# Power.net
KiCad netlist of a schematic drawn in Altium Designer
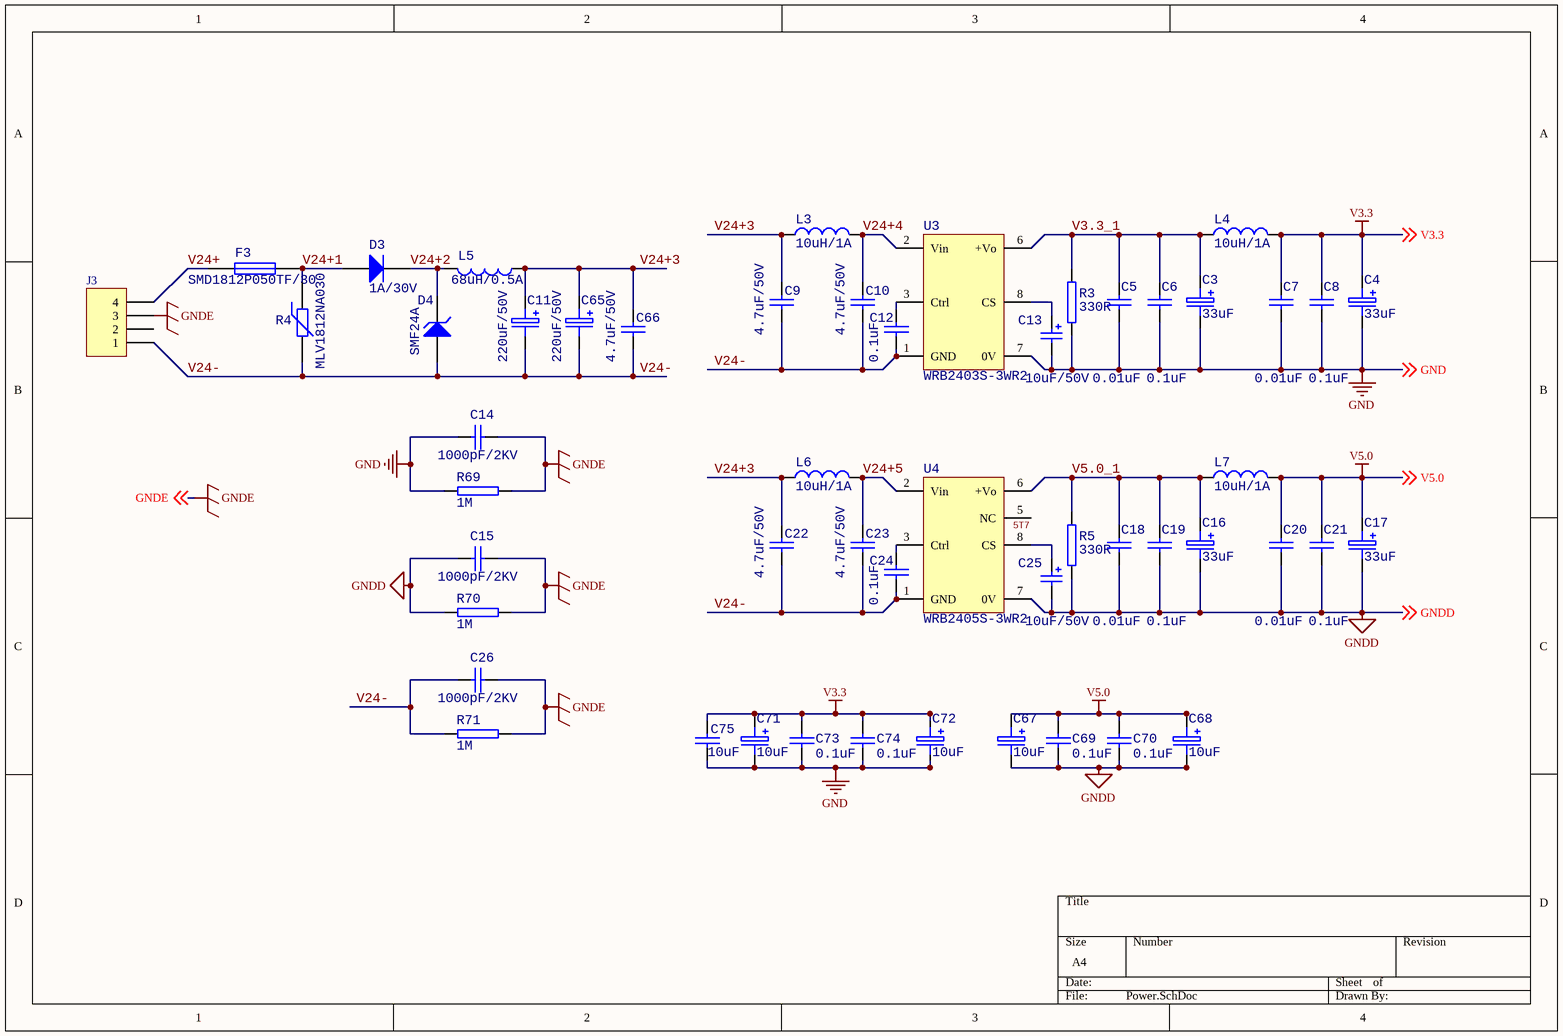
[diagram p0: Power.SchDoc]

(export (version "E")
  (design (tool "Eeschema 10.0.6"))
  (components
    (comp (ref "C3")
      (value "33uF")
      (footprint "C3528(B)")
      (description "CA45-?V?uF ABCD 16V10UF[A型3210]16V22UF(B型1210) 16V47UF(C型1812)")
      (libsource (lib "input") (part "CAPACITOR POL"))
    )
    (comp (ref "C4")
      (value "33uF")
      (footprint "C3528(B)")
      (description "CA45-?V?uF ABCD 16V10UF[A型3210]16V22UF(B型1210) 16V47UF(C型1812)")
      (libsource (lib "input") (part "CAPACITOR POL"))
    )
    (comp (ref "C5")
      (value "0.01uF")
      (footprint "C1608(0603)")
      (description "Capacitor")
      (libsource (lib "input") (part "CAP"))
    )
    (comp (ref "C6")
      (value "0.1uF")
      (footprint "C1608(0603)")
      (description "Capacitor")
      (libsource (lib "input") (part "CAP"))
    )
    (comp (ref "C7")
      (value "0.01uF")
      (footprint "C1608(0603)")
      (description "Capacitor")
      (libsource (lib "input") (part "CAP"))
    )
    (comp (ref "C8")
      (value "0.1uF")
      (footprint "C1608(0603)")
      (description "Capacitor")
      (libsource (lib "input") (part "CAP"))
    )
    (comp (ref "C9")
      (value "4.7uF/50V")
      (footprint "C2012(0805)")
      (description "Capacitor")
      (libsource (lib "input") (part "CAP"))
    )
    (comp (ref "C10")
      (value "4.7uF/50V")
      (footprint "C2012(0805)")
      (description "Capacitor")
      (libsource (lib "input") (part "CAP"))
    )
    (comp (ref "C11")
      (value "220uF/50V")
      (footprint "CAPMP10X120")
      (description "CA45-?V?uF ABCD 16V10UF[A型3210]16V22UF(B型1210) 16V47UF(C型1812)")
      (libsource (lib "input") (part "CAPACITOR POL"))
    )
    (comp (ref "C12")
      (value "0.1uF")
      (footprint "C1608(0603)")
      (description "Capacitor")
      (libsource (lib "input") (part "CAP"))
    )
    (comp (ref "C13")
      (value "10uF/50V")
      (footprint "C3216(1206)")
      (description "Polarized Capacitor (Axial)")
      (fields (field (name "PUBLISHER") "Altium Limited"))
      (libsource (lib "Miscellaneous Devices") (part "Cap Pol2"))
    )
    (comp (ref "C14")
      (value "1000pF/2KV")
      (footprint "C3216(1206)")
      (description "Capacitor")
      (libsource (lib "input") (part "CAP"))
    )
    (comp (ref "C15")
      (value "1000pF/2KV")
      (footprint "C3216(1206)")
      (description "Capacitor")
      (libsource (lib "input") (part "CAP"))
    )
    (comp (ref "C16")
      (value "33uF")
      (footprint "C3528(B)")
      (description "CA45-?V?uF ABCD 16V10UF[A型3210]16V22UF(B型1210) 16V47UF(C型1812)")
      (libsource (lib "input") (part "CAPACITOR POL"))
    )
    (comp (ref "C17")
      (value "33uF")
      (footprint "C3528(B)")
      (description "CA45-?V?uF ABCD 16V10UF[A型3210]16V22UF(B型1210) 16V47UF(C型1812)")
      (libsource (lib "input") (part "CAPACITOR POL"))
    )
    (comp (ref "C18")
      (value "0.01uF")
      (footprint "C1608(0603)")
      (description "Capacitor")
      (libsource (lib "input") (part "CAP"))
    )
    (comp (ref "C19")
      (value "0.1uF")
      (footprint "C1608(0603)")
      (description "Capacitor")
      (libsource (lib "input") (part "CAP"))
    )
    (comp (ref "C20")
      (value "0.01uF")
      (footprint "C1608(0603)")
      (description "Capacitor")
      (libsource (lib "input") (part "CAP"))
    )
    (comp (ref "C21")
      (value "0.1uF")
      (footprint "C1608(0603)")
      (description "Capacitor")
      (libsource (lib "input") (part "CAP"))
    )
    (comp (ref "C22")
      (value "4.7uF/50V")
      (footprint "C2012(0805)")
      (description "Capacitor")
      (libsource (lib "input") (part "CAP"))
    )
    (comp (ref "C23")
      (value "4.7uF/50V")
      (footprint "C2012(0805)")
      (description "Capacitor")
      (libsource (lib "input") (part "CAP"))
    )
    (comp (ref "C24")
      (value "0.1uF")
      (footprint "C1608(0603)")
      (description "Capacitor")
      (libsource (lib "input") (part "CAP"))
    )
    (comp (ref "C25")
      (value "10uF/50V")
      (footprint "C3216(1206)")
      (description "Polarized Capacitor (Axial)")
      (fields (field (name "PUBLISHER") "Altium Limited"))
      (libsource (lib "Miscellaneous Devices") (part "Cap Pol2"))
    )
    (comp (ref "C26")
      (value "1000pF/2KV")
      (footprint "C3216(1206)")
      (description "Capacitor")
      (libsource (lib "input") (part "CAP"))
    )
    (comp (ref "C65")
      (value "220uF/50V")
      (footprint "CAPMP10X120")
      (description "CA45-?V?uF ABCD 16V10UF[A型3210]16V22UF(B型1210) 16V47UF(C型1812)")
      (libsource (lib "input") (part "CAPACITOR POL"))
    )
    (comp (ref "C66")
      (value "4.7uF/50V")
      (footprint "C2012(0805)")
      (description "Capacitor")
      (libsource (lib "input") (part "CAP"))
    )
    (comp (ref "C67")
      (value "10uF")
      (footprint "C3216(A)")
      (description "CA45-?V?uF ABCD 16V10UF[A型3210]16V22UF(B型1210) 16V47UF(C型1812)")
      (libsource (lib "input") (part "CAPACITOR POL"))
    )
    (comp (ref "C68")
      (value "10uF")
      (footprint "C3216(A)")
      (description "CA45-?V?uF ABCD 16V10UF[A型3210]16V22UF(B型1210) 16V47UF(C型1812)")
      (libsource (lib "input") (part "CAPACITOR POL"))
    )
    (comp (ref "C69")
      (value "0.1uF")
      (footprint "C1608(0603)")
      (description "Capacitor")
      (libsource (lib "input") (part "CAP"))
    )
    (comp (ref "C70")
      (value "0.1uF")
      (footprint "C1608(0603)")
      (description "Capacitor")
      (libsource (lib "input") (part "CAP"))
    )
    (comp (ref "C71")
      (value "10uF")
      (footprint "C3216(A)")
      (description "CA45-?V?uF ABCD 16V10UF[A型3210]16V22UF(B型1210) 16V47UF(C型1812)")
      (libsource (lib "input") (part "CAPACITOR POL"))
    )
    (comp (ref "C72")
      (value "10uF")
      (footprint "C3216(A)")
      (description "CA45-?V?uF ABCD 16V10UF[A型3210]16V22UF(B型1210) 16V47UF(C型1812)")
      (libsource (lib "input") (part "CAPACITOR POL"))
    )
    (comp (ref "C73")
      (value "0.1uF")
      (footprint "C1608(0603)")
      (description "Capacitor")
      (libsource (lib "input") (part "CAP"))
    )
    (comp (ref "C74")
      (value "0.1uF")
      (footprint "C1608(0603)")
      (description "Capacitor")
      (libsource (lib "input") (part "CAP"))
    )
    (comp (ref "C75")
      (value "10uF")
      (footprint "C2012(0805)")
      (description "Capacitor")
      (libsource (lib "input") (part "CAP"))
    )
    (comp (ref "D3")
      (value "1A/30V")
      (footprint "SOD323")
      (description "Default Diode")
      (fields (field (name "PUBLISHER") "Altium Limited"))
      (libsource (lib "Miscellaneous Devices") (part "Diode"))
    )
    (comp (ref "D4")
      (value "SMF24A")
      (footprint "SOD123")
      (description "Zener Diode")
      (fields (field (name "PUBLISHER") "Altium Limited"))
      (libsource (lib "Miscellaneous Devices") (part "D Zener"))
    )
    (comp (ref "F3")
      (value "SMD1812P050TF/30")
      (footprint "R4532(1812)")
      (description "Fuse")
      (libsource (lib "*") (part "FUSE1"))
    )
    (comp (ref "J3")
      (value "Header 4")
      (footprint "MSTBO2.5/4-G1R")
      (description "Header, 4-Pin")
      (fields (field (name "PUBLISHER") "Altium Limited"))
      (libsource (lib "Miscellaneous Connectors") (part "Header 4"))
    )
    (comp (ref "L3")
      (value "10uH/1A")
      (footprint "L4040")
      (description "Inductor")
      (fields (field (name "PUBLISHER") "Altium Limited"))
      (libsource (lib "Miscellaneous Devices") (part "Inductor"))
    )
    (comp (ref "L4")
      (value "10uH/1A")
      (footprint "L4040")
      (description "Inductor")
      (fields (field (name "PUBLISHER") "Altium Limited"))
      (libsource (lib "Miscellaneous Devices") (part "Inductor"))
    )
    (comp (ref "L5")
      (value "68uH/0.5A")
      (footprint "L4040")
      (description "Inductor")
      (fields (field (name "PUBLISHER") "Altium Limited"))
      (libsource (lib "Miscellaneous Devices") (part "Inductor"))
    )
    (comp (ref "L6")
      (value "10uH/1A")
      (footprint "L4040")
      (description "Inductor")
      (fields (field (name "PUBLISHER") "Altium Limited"))
      (libsource (lib "Miscellaneous Devices") (part "Inductor"))
    )
    (comp (ref "L7")
      (value "10uH/1A")
      (footprint "L4040")
      (description "Inductor")
      (fields (field (name "PUBLISHER") "Altium Limited"))
      (libsource (lib "Miscellaneous Devices") (part "Inductor"))
    )
    (comp (ref "R3") (value "330R") (footprint "R3216(1206)") (libsource (lib "motor") (part "R")))
    (comp (ref "R4")
      (value "MLV1812NA030")
      (footprint "R4532(1812)")
      (description "Varistor (Voltage-Sensitive Resistor)")
      (fields (field (name "PUBLISHER") "Altium Limited"))
      (libsource (lib "Miscellaneous Devices") (part "Res Varistor"))
    )
    (comp (ref "R5") (value "330R") (footprint "R3216(1206)") (libsource (lib "motor") (part "R")))
    (comp (ref "R69") (value "1M") (footprint "R3216(1206)") (libsource (lib "motor") (part "R")))
    (comp (ref "R70") (value "1M") (footprint "R3216(1206)") (libsource (lib "motor") (part "R")))
    (comp (ref "R71") (value "1M") (footprint "R3216(1206)") (libsource (lib "motor") (part "R")))
    (comp (ref "U3")
      (value "WRB2403S-3WR2")
      (footprint "SIP8")
      (libsource (lib "SL-DPT100") (part "WRA_S-1WR2"))
    )
    (comp (ref "U4")
      (value "WRB2405S-3WR2")
      (footprint "SIP8")
      (libsource (lib "SL-DPT100") (part "WRA_S-1WR2"))
    )
  )
  (nets
    (net (code "1") (name "/5T7") (class "Default")
      (node (ref "U4") (pin "5") (pinfunction "NC_5") (pintype "passive"))
    )
    (net (code "2") (name "/V3.3_1") (class "Default")
      (node (ref "C3") (pin "1") (pinfunction "1_1") (pintype "passive"))
      (node (ref "C5") (pin "2") (pinfunction "2_2") (pintype "passive"))
      (node (ref "C6") (pin "2") (pinfunction "2_2") (pintype "passive"))
      (node (ref "L4") (pin "1") (pinfunction "1_1") (pintype "passive"))
      (node (ref "R3") (pin "1") (pinfunction "1_1") (pintype "passive"))
      (node (ref "U3") (pin "6") (pinfunction "+Vo_6") (pintype "passive"))
    )
    (net (code "3") (name "/V5.0_1") (class "Default")
      (node (ref "C16") (pin "1") (pinfunction "1_1") (pintype "passive"))
      (node (ref "C18") (pin "2") (pinfunction "2_2") (pintype "passive"))
      (node (ref "C19") (pin "2") (pinfunction "2_2") (pintype "passive"))
      (node (ref "L7") (pin "1") (pinfunction "1_1") (pintype "passive"))
      (node (ref "R5") (pin "1") (pinfunction "1_1") (pintype "passive"))
      (node (ref "U4") (pin "6") (pinfunction "+Vo_6") (pintype "passive"))
    )
    (net (code "4") (name "/V24+") (class "Default")
      (node (ref "F3") (pin "1") (pinfunction "1_1") (pintype "passive"))
      (node (ref "J3") (pin "4") (pinfunction "4_4") (pintype "passive"))
    )
    (net (code "5") (name "/V24+1") (class "Default")
      (node (ref "D3") (pin "1") (pinfunction "A_1") (pintype "passive"))
      (node (ref "F3") (pin "2") (pinfunction "2_2") (pintype "passive"))
      (node (ref "R4") (pin "1") (pinfunction "1_1") (pintype "passive"))
    )
    (net (code "6") (name "/V24+2") (class "Default")
      (node (ref "D3") (pin "2") (pinfunction "K_2") (pintype "passive"))
      (node (ref "D4") (pin "2") (pinfunction "K_2") (pintype "passive"))
      (node (ref "L5") (pin "2") (pinfunction "2_2") (pintype "passive"))
    )
    (net (code "7") (name "/V24+3") (class "Default")
      (node (ref "C11") (pin "1") (pinfunction "1_1") (pintype "passive"))
      (node (ref "C22") (pin "2") (pinfunction "2_2") (pintype "passive"))
      (node (ref "C65") (pin "1") (pinfunction "1_1") (pintype "passive"))
      (node (ref "C66") (pin "2") (pinfunction "2_2") (pintype "passive"))
      (node (ref "C9") (pin "2") (pinfunction "2_2") (pintype "passive"))
      (node (ref "L3") (pin "1") (pinfunction "1_1") (pintype "passive"))
      (node (ref "L5") (pin "1") (pinfunction "1_1") (pintype "passive"))
      (node (ref "L6") (pin "1") (pinfunction "1_1") (pintype "passive"))
    )
    (net (code "8") (name "/V24+4") (class "Default")
      (node (ref "C10") (pin "2") (pinfunction "2_2") (pintype "passive"))
      (node (ref "L3") (pin "2") (pinfunction "2_2") (pintype "passive"))
      (node (ref "U3") (pin "2") (pinfunction "Vin_2") (pintype "passive"))
    )
    (net (code "9") (name "/V24+5") (class "Default")
      (node (ref "C23") (pin "2") (pinfunction "2_2") (pintype "passive"))
      (node (ref "L6") (pin "2") (pinfunction "2_2") (pintype "passive"))
      (node (ref "U4") (pin "2") (pinfunction "Vin_2") (pintype "passive"))
    )
    (net (code "10") (name "/V24-") (class "Default")
      (node (ref "C10") (pin "1") (pinfunction "1_1") (pintype "passive"))
      (node (ref "C11") (pin "2") (pinfunction "2_2") (pintype "passive"))
      (node (ref "C12") (pin "2") (pinfunction "2_2") (pintype "passive"))
      (node (ref "C22") (pin "1") (pinfunction "1_1") (pintype "passive"))
      (node (ref "C23") (pin "1") (pinfunction "1_1") (pintype "passive"))
      (node (ref "C24") (pin "2") (pinfunction "2_2") (pintype "passive"))
      (node (ref "C26") (pin "1") (pinfunction "1_1") (pintype "passive"))
      (node (ref "C65") (pin "2") (pinfunction "2_2") (pintype "passive"))
      (node (ref "C66") (pin "1") (pinfunction "1_1") (pintype "passive"))
      (node (ref "C9") (pin "1") (pinfunction "1_1") (pintype "passive"))
      (node (ref "D4") (pin "1") (pinfunction "A_1") (pintype "passive"))
      (node (ref "J3") (pin "1") (pinfunction "1_1") (pintype "passive"))
      (node (ref "R4") (pin "2") (pinfunction "2_2") (pintype "passive"))
      (node (ref "R71") (pin "1") (pinfunction "1_1") (pintype "passive"))
      (node (ref "U3") (pin "1") (pinfunction "GND_1") (pintype "passive"))
      (node (ref "U4") (pin "1") (pinfunction "GND_1") (pintype "passive"))
    )
    (net (code "11") (name "GND") (class "Default")
      (node (ref "C13") (pin "2") (pinfunction "2_2") (pintype "passive"))
      (node (ref "C14") (pin "1") (pinfunction "1_1") (pintype "passive"))
      (node (ref "C3") (pin "2") (pinfunction "2_2") (pintype "passive"))
      (node (ref "C4") (pin "2") (pinfunction "2_2") (pintype "passive"))
      (node (ref "C5") (pin "1") (pinfunction "1_1") (pintype "passive"))
      (node (ref "C6") (pin "1") (pinfunction "1_1") (pintype "passive"))
      (node (ref "C7") (pin "1") (pinfunction "1_1") (pintype "passive"))
      (node (ref "C71") (pin "2") (pinfunction "2_2") (pintype "passive"))
      (node (ref "C72") (pin "2") (pinfunction "2_2") (pintype "passive"))
      (node (ref "C73") (pin "1") (pinfunction "1_1") (pintype "passive"))
      (node (ref "C74") (pin "1") (pinfunction "1_1") (pintype "passive"))
      (node (ref "C75") (pin "1") (pinfunction "1_1") (pintype "passive"))
      (node (ref "C8") (pin "1") (pinfunction "1_1") (pintype "passive"))
      (node (ref "R3") (pin "2") (pinfunction "2_2") (pintype "passive"))
      (node (ref "R69") (pin "1") (pinfunction "1_1") (pintype "passive"))
      (node (ref "U3") (pin "7") (pinfunction "0V_7") (pintype "passive"))
    )
    (net (code "12") (name "GNDD") (class "Default")
      (node (ref "C15") (pin "1") (pinfunction "1_1") (pintype "passive"))
      (node (ref "C16") (pin "2") (pinfunction "2_2") (pintype "passive"))
      (node (ref "C17") (pin "2") (pinfunction "2_2") (pintype "passive"))
      (node (ref "C18") (pin "1") (pinfunction "1_1") (pintype "passive"))
      (node (ref "C19") (pin "1") (pinfunction "1_1") (pintype "passive"))
      (node (ref "C20") (pin "1") (pinfunction "1_1") (pintype "passive"))
      (node (ref "C21") (pin "1") (pinfunction "1_1") (pintype "passive"))
      (node (ref "C25") (pin "2") (pinfunction "2_2") (pintype "passive"))
      (node (ref "C67") (pin "2") (pinfunction "2_2") (pintype "passive"))
      (node (ref "C68") (pin "2") (pinfunction "2_2") (pintype "passive"))
      (node (ref "C69") (pin "1") (pinfunction "1_1") (pintype "passive"))
      (node (ref "C70") (pin "1") (pinfunction "1_1") (pintype "passive"))
      (node (ref "R5") (pin "2") (pinfunction "2_2") (pintype "passive"))
      (node (ref "R70") (pin "1") (pinfunction "1_1") (pintype "passive"))
      (node (ref "U4") (pin "7") (pinfunction "0V_7") (pintype "passive"))
    )
    (net (code "13") (name "GNDE") (class "Default")
      (node (ref "C14") (pin "2") (pinfunction "2_2") (pintype "passive"))
      (node (ref "C15") (pin "2") (pinfunction "2_2") (pintype "passive"))
      (node (ref "C26") (pin "2") (pinfunction "2_2") (pintype "passive"))
      (node (ref "J3") (pin "3") (pinfunction "3_3") (pintype "passive"))
      (node (ref "R69") (pin "2") (pinfunction "2_2") (pintype "passive"))
      (node (ref "R70") (pin "2") (pinfunction "2_2") (pintype "passive"))
      (node (ref "R71") (pin "2") (pinfunction "2_2") (pintype "passive"))
    )
    (net (code "14") (name "Net-(U3-CS)") (class "Default")
      (node (ref "C13") (pin "1") (pinfunction "1_1") (pintype "passive"))
      (node (ref "U3") (pin "8") (pinfunction "CS_8") (pintype "passive"))
    )
    (net (code "15") (name "Net-(U3-Ctrl)") (class "Default")
      (node (ref "C12") (pin "1") (pinfunction "1_1") (pintype "passive"))
      (node (ref "U3") (pin "3") (pinfunction "Ctrl_3") (pintype "passive"))
    )
    (net (code "16") (name "Net-(U4-CS)") (class "Default")
      (node (ref "C25") (pin "1") (pinfunction "1_1") (pintype "passive"))
      (node (ref "U4") (pin "8") (pinfunction "CS_8") (pintype "passive"))
    )
    (net (code "17") (name "Net-(U4-Ctrl)") (class "Default")
      (node (ref "C24") (pin "1") (pinfunction "1_1") (pintype "passive"))
      (node (ref "U4") (pin "3") (pinfunction "Ctrl_3") (pintype "passive"))
    )
    (net (code "18") (name "V3.3") (class "Default")
      (node (ref "C4") (pin "1") (pinfunction "1_1") (pintype "passive"))
      (node (ref "C7") (pin "2") (pinfunction "2_2") (pintype "passive"))
      (node (ref "C71") (pin "1") (pinfunction "1_1") (pintype "passive"))
      (node (ref "C72") (pin "1") (pinfunction "1_1") (pintype "passive"))
      (node (ref "C73") (pin "2") (pinfunction "2_2") (pintype "passive"))
      (node (ref "C74") (pin "2") (pinfunction "2_2") (pintype "passive"))
      (node (ref "C75") (pin "2") (pinfunction "2_2") (pintype "passive"))
      (node (ref "C8") (pin "2") (pinfunction "2_2") (pintype "passive"))
      (node (ref "L4") (pin "2") (pinfunction "2_2") (pintype "passive"))
    )
    (net (code "19") (name "V5.0") (class "Default")
      (node (ref "C17") (pin "1") (pinfunction "1_1") (pintype "passive"))
      (node (ref "C20") (pin "2") (pinfunction "2_2") (pintype "passive"))
      (node (ref "C21") (pin "2") (pinfunction "2_2") (pintype "passive"))
      (node (ref "C67") (pin "1") (pinfunction "1_1") (pintype "passive"))
      (node (ref "C68") (pin "1") (pinfunction "1_1") (pintype "passive"))
      (node (ref "C69") (pin "2") (pinfunction "2_2") (pintype "passive"))
      (node (ref "C70") (pin "2") (pinfunction "2_2") (pintype "passive"))
      (node (ref "L7") (pin "2") (pinfunction "2_2") (pintype "passive"))
    )
    (net (code "20") (name "unconnected-(J3-Pad2)") (class "Default")
      (node (ref "J3") (pin "2") (pinfunction "2_2") (pintype "passive"))
    )
    (net (code "21") (name "unconnected-(U3-NC-Pad5)") (class "Default")
      (node (ref "U3") (pin "5") (pinfunction "NC_5") (pintype "passive"))
    )
  )
)
